# JRDFinalSchem.net
KiCad netlist of a schematic drawn in Altium Designer
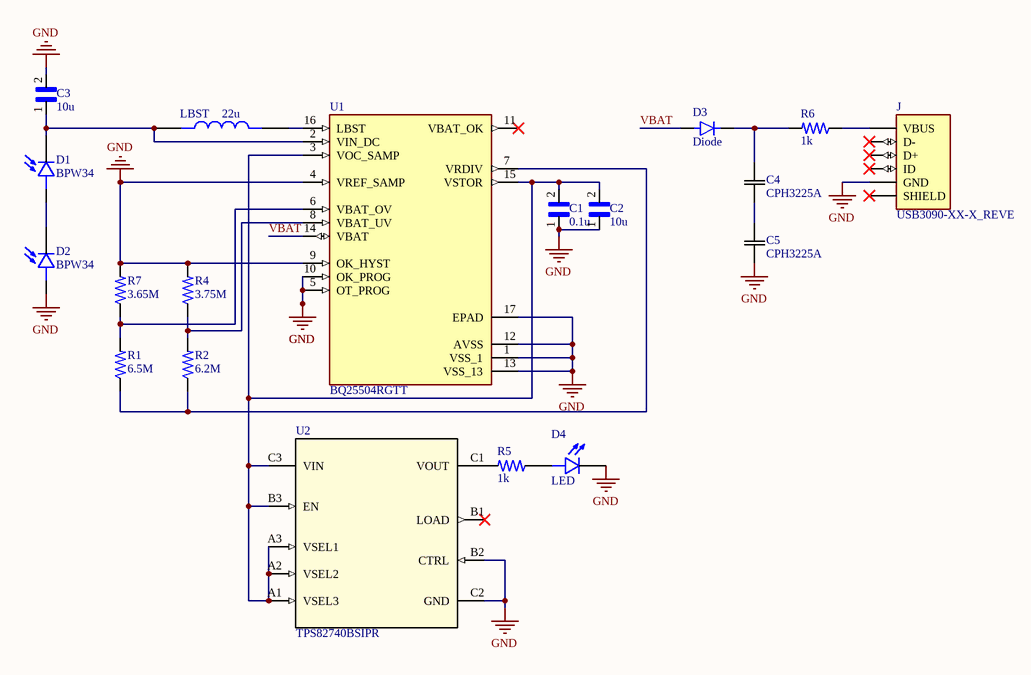
[diagram p0: JRDFinalSchem.SchDoc]

(export (version "E")
  (design (tool "Eeschema 10.0.6"))
  (components
    (comp (ref "C1")
      (value "0.1u")
      (footprint "LED")
      (description "Capacitor")
      (fields (field (name "MF") "Samsung") (field (name "MP") "CL21A106KAYNNNE"))
      (libsource (lib "JRDFinal") (part "Capacitor"))
    )
    (comp (ref "C2")
      (value "10u")
      (footprint "LED")
      (description "Capacitor")
      (fields (field (name "MF") "Samsung") (field (name "MP") "CL21A106KAYNNNE"))
      (libsource (lib "JRDFinal") (part "Capacitor"))
    )
    (comp (ref "C3")
      (value "10u")
      (footprint "LED")
      (description "Capacitor")
      (fields (field (name "MF") "Samsung") (field (name "MP") "CL21A106KAYNNNE"))
      (libsource (lib "JRDFinal") (part "Capacitor"))
    )
    (comp (ref "C4")
      (value "CPH3225A")
      (footprint "CAP_CPH3225A_EPS")
      (description "No Description Available")
      (fields (field (name "COPYRIGHT") "Copyright (C) 2022 Ultra Librarian. All rights reserved."))
      (libsource (lib "Schlib1") (part "CPH3225A"))
    )
    (comp (ref "C5")
      (value "CPH3225A")
      (footprint "CAP_CPH3225A_EPS")
      (description "No Description Available")
      (fields (field (name "COPYRIGHT") "Copyright (C) 2022 Ultra Librarian. All rights reserved."))
      (libsource (lib "Schlib1") (part "CPH3225A"))
    )
    (comp (ref "D1")
      (value "BPW34")
      (footprint "DIO_BPW34")
      (description "Photodiode 900nm  130Â° 2-DIP (0.200, 5.10mm)")
      (fields (field (name "MF") "Vishay Semiconductors"))
      (libsource (lib "Schlib1") (part "BPW34"))
    )
    (comp (ref "D2")
      (value "BPW34")
      (footprint "DIO_BPW34")
      (description "Photodiode 900nm  130Â° 2-DIP (0.200, 5.10mm)")
      (fields (field (name "MF") "Vishay Semiconductors"))
      (libsource (lib "Schlib1") (part "BPW34"))
    )
    (comp (ref "D3")
      (value "Diode")
      (footprint "LED")
      (description "Diode Standard 1000V 1A Through Hole DO-204AL _DO-41_")
      (fields (field (name "MF") "ON Semiconductor") (field (name "MP") "1N4007"))
      (libsource (lib "JRDFinal") (part "Diode"))
    )
    (comp (ref "D4")
      (value "LED")
      (footprint "LED")
      (description "Red 623nm LED Indication - Discrete 1.9V Radial")
      (fields (field (name "MF") "Wurth Electronics") (field (name "MP") "151054RS03000"))
      (libsource (lib "JRDFinal") (part "LED"))
    )
    (comp (ref "J")
      (value "USB3090-XX-X_REVE")
      (footprint "GCT_USB3090-XX-X_REVE")
      (description "USB - micro AB USB 2.0 Receptacle Connector 5 Position Surface Mount, Right Angle; Through Hole")
      (fields (field (name "MP") "USB3090-30-A") (field (name "MF") "Global Connector Technology"))
      (libsource (lib "JRDFinal") (part "USB3090-XX-X_REVE"))
    )
    (comp (ref "LBST")
      (value "22u")
      (footprint "Inductor")
      (description "Line Inductors for RECOM Power Supply")
      (fields (field (name "MP") "RLS-186-R") (field (name "MF") "Recom Power"))
      (libsource (lib "JRDFinal") (part "Inductor"))
    )
    (comp (ref "R1")
      (value "6.5M")
      (footprint "LED")
      (description "0805")
      (fields (field (name "DIGI-KEY_PART_NUMBER") "541-1901-1-ND") (field (name "MF") "Vishay Dale"))
      (libsource (lib "Schlib1") (part "Resistor"))
    )
    (comp (ref "R2")
      (value "6.2M")
      (footprint "LED")
      (description "0805")
      (fields (field (name "DIGI-KEY_PART_NUMBER") "541-1901-1-ND") (field (name "MF") "Vishay Dale"))
      (libsource (lib "Schlib1") (part "Resistor"))
    )
    (comp (ref "R4")
      (value "3.75M")
      (footprint "LED")
      (description "0805")
      (fields (field (name "DIGI-KEY_PART_NUMBER") "541-1901-1-ND") (field (name "MF") "Vishay Dale"))
      (libsource (lib "Schlib1") (part "Resistor"))
    )
    (comp (ref "R5")
      (value "1k")
      (footprint "LED")
      (description "0805")
      (fields (field (name "DIGI-KEY_PART_NUMBER") "541-1901-1-ND") (field (name "MF") "Vishay Dale"))
      (libsource (lib "Schlib1") (part "Resistor"))
    )
    (comp (ref "R6")
      (value "1k")
      (footprint "LED")
      (description "0805")
      (fields (field (name "DIGI-KEY_PART_NUMBER") "541-1901-1-ND") (field (name "MF") "Vishay Dale"))
      (libsource (lib "Schlib1") (part "Resistor"))
    )
    (comp (ref "R7")
      (value "3.65M")
      (footprint "LED")
      (description "0805")
      (fields (field (name "DIGI-KEY_PART_NUMBER") "541-1901-1-ND") (field (name "MF") "Vishay Dale"))
      (libsource (lib "Schlib1") (part "Resistor"))
    )
    (comp (ref "U1")
      (value "BQ25504RGTT")
      (footprint "QFN50P300X300X100-17N")
      (libsource (lib "Schlib1") (part "BQ25504RGTT"))
    )
    (comp (ref "U2")
      (value "TPS82740BSIPR")
      (footprint "SIP0009F")
      (description "No Description Available")
      (fields (field (name "COPYRIGHT") "Copyright (C) 2022 Ultra Librarian. All rights reserved."))
      (libsource (lib "Schlib1") (part "TPS82740BSIPR"))
    )
  )
  (nets
    (net (code "1") (name "/VBAT") (class "Default")
      (node (ref "D3") (pin "1") (pinfunction "A_1") (pintype "passive"))
      (node (ref "U1") (pin "14") (pinfunction "VBAT_14") (pintype "bidirectional"))
    )
    (net (code "2") (name "GND") (class "Default")
      (node (ref "C1") (pin "1") (pinfunction "1_1") (pintype "passive"))
      (node (ref "C2") (pin "1") (pinfunction "1_1") (pintype "passive"))
      (node (ref "C3") (pin "2") (pinfunction "2_2") (pintype "passive"))
      (node (ref "C5") (pin "1") (pinfunction "1_1") (pintype "passive"))
      (node (ref "D2") (pin "A") (pinfunction "A_A") (pintype "passive"))
      (node (ref "D4") (pin "2") (pinfunction "C_2") (pintype "passive"))
      (node (ref "J") (pin "5") (pinfunction "GND_5") (pintype "power_in"))
      (node (ref "R4") (pin "2") (pinfunction "2_2") (pintype "passive"))
      (node (ref "R7") (pin "2") (pinfunction "2_2") (pintype "passive"))
      (node (ref "U1") (pin "1") (pinfunction "VSS_1_1") (pintype "power_in"))
      (node (ref "U1") (pin "10") (pinfunction "OK_PROG_10") (pintype "input"))
      (node (ref "U1") (pin "12") (pinfunction "AVSS_12") (pintype "power_in"))
      (node (ref "U1") (pin "13") (pinfunction "VSS_13_13") (pintype "power_in"))
      (node (ref "U1") (pin "17") (pinfunction "EPAD_17") (pintype "power_in"))
      (node (ref "U1") (pin "4") (pinfunction "VREF_SAMP_4") (pintype "input"))
      (node (ref "U1") (pin "5") (pinfunction "OT_PROG_5") (pintype "input"))
      (node (ref "U1") (pin "9") (pinfunction "OK_HYST_9") (pintype "input"))
      (node (ref "U2") (pin "B2") (pinfunction "CTRL_B2") (pintype "input"))
      (node (ref "U2") (pin "C2") (pinfunction "GND_C2") (pintype "power_in"))
    )
    (net (code "3") (name "Net-(C4-Pad1)") (class "Default")
      (node (ref "C4") (pin "1") (pinfunction "1_1") (pintype "passive"))
      (node (ref "C5") (pin "2") (pinfunction "2_2") (pintype "passive"))
    )
    (net (code "4") (name "Net-(D1-PadA)") (class "Default")
      (node (ref "D1") (pin "A") (pinfunction "A_A") (pintype "passive"))
      (node (ref "D2") (pin "C") (pinfunction "C_C") (pintype "passive"))
    )
    (net (code "5") (name "Net-(D3-C)") (class "Default")
      (node (ref "C4") (pin "2") (pinfunction "2_2") (pintype "passive"))
      (node (ref "D3") (pin "2") (pinfunction "C_2") (pintype "passive"))
      (node (ref "R6") (pin "2") (pinfunction "2_2") (pintype "passive"))
    )
    (net (code "6") (name "Net-(D4-A)") (class "Default")
      (node (ref "D4") (pin "1") (pinfunction "A_1") (pintype "passive"))
      (node (ref "R5") (pin "1") (pinfunction "1_1") (pintype "passive"))
    )
    (net (code "7") (name "Net-(J-VBUS)") (class "Default")
      (node (ref "J") (pin "1") (pinfunction "VBUS_1") (pintype "power_in"))
      (node (ref "R6") (pin "1") (pinfunction "1_1") (pintype "passive"))
    )
    (net (code "8") (name "Net-(U1-LBST)") (class "Default")
      (node (ref "LBST") (pin "2") (pinfunction "2_2") (pintype "passive"))
      (node (ref "U1") (pin "16") (pinfunction "LBST_16") (pintype "input"))
    )
    (net (code "9") (name "Net-(U1-VBAT_OV)") (class "Default")
      (node (ref "R1") (pin "2") (pinfunction "2_2") (pintype "passive"))
      (node (ref "R7") (pin "1") (pinfunction "1_1") (pintype "passive"))
      (node (ref "U1") (pin "6") (pinfunction "VBAT_OV_6") (pintype "input"))
    )
    (net (code "10") (name "Net-(U1-VBAT_UV)") (class "Default")
      (node (ref "R2") (pin "2") (pinfunction "2_2") (pintype "passive"))
      (node (ref "R4") (pin "1") (pinfunction "1_1") (pintype "passive"))
      (node (ref "U1") (pin "8") (pinfunction "VBAT_UV_8") (pintype "input"))
    )
    (net (code "11") (name "Net-(U1-VIN_DC)") (class "Default")
      (node (ref "C3") (pin "1") (pinfunction "1_1") (pintype "passive"))
      (node (ref "D1") (pin "C") (pinfunction "C_C") (pintype "passive"))
      (node (ref "LBST") (pin "1") (pinfunction "1_1") (pintype "passive"))
      (node (ref "U1") (pin "2") (pinfunction "VIN_DC_2") (pintype "input"))
    )
    (net (code "12") (name "Net-(U1-VOC_SAMP)") (class "Default")
      (node (ref "C1") (pin "2") (pinfunction "2_2") (pintype "passive"))
      (node (ref "C2") (pin "2") (pinfunction "2_2") (pintype "passive"))
      (node (ref "U1") (pin "15") (pinfunction "VSTOR_15") (pintype "output"))
      (node (ref "U1") (pin "3") (pinfunction "VOC_SAMP_3") (pintype "input"))
      (node (ref "U2") (pin "A1") (pinfunction "VSEL3_A1") (pintype "input"))
      (node (ref "U2") (pin "A2") (pinfunction "VSEL2_A2") (pintype "input"))
      (node (ref "U2") (pin "A3") (pinfunction "VSEL1_A3") (pintype "input"))
      (node (ref "U2") (pin "B3") (pinfunction "EN_B3") (pintype "input"))
      (node (ref "U2") (pin "C3") (pinfunction "VIN_C3") (pintype "power_in"))
    )
    (net (code "13") (name "Net-(U1-VRDIV)") (class "Default")
      (node (ref "R1") (pin "1") (pinfunction "1_1") (pintype "passive"))
      (node (ref "R2") (pin "1") (pinfunction "1_1") (pintype "passive"))
      (node (ref "U1") (pin "7") (pinfunction "VRDIV_7") (pintype "output"))
    )
    (net (code "14") (name "Net-(U2-VOUT)") (class "Default")
      (node (ref "R5") (pin "2") (pinfunction "2_2") (pintype "passive"))
      (node (ref "U2") (pin "C1") (pinfunction "VOUT_C1") (pintype "power_in"))
    )
    (net (code "15") (name "unconnected-(J-D+-Pad3)") (class "Default")
      (node (ref "J") (pin "3") (pinfunction "D+_3") (pintype "bidirectional+no_connect"))
    )
    (net (code "16") (name "unconnected-(J-D--Pad2)") (class "Default")
      (node (ref "J") (pin "2") (pinfunction "D-_2") (pintype "bidirectional+no_connect"))
    )
    (net (code "17") (name "unconnected-(J-ID-Pad4)") (class "Default")
      (node (ref "J") (pin "4") (pinfunction "ID_4") (pintype "bidirectional+no_connect"))
    )
    (net (code "18") (name "unconnected-(J-SHIELD-Pad7)") (class "Default")
      (node (ref "J") (pin "7") (pinfunction "SHIELD_7") (pintype "power_in+no_connect"))
    )
    (net (code "19") (name "unconnected-(U1-VBAT_OK-Pad11)") (class "Default")
      (node (ref "U1") (pin "11") (pinfunction "VBAT_OK_11") (pintype "output+no_connect"))
    )
    (net (code "20") (name "unconnected-(U2-LOAD-PadB1)") (class "Default")
      (node (ref "U2") (pin "B1") (pinfunction "LOAD_B1") (pintype "output+no_connect"))
    )
  )
)
